# Bus.net
KiCad netlist of a schematic drawn in Altium Designer
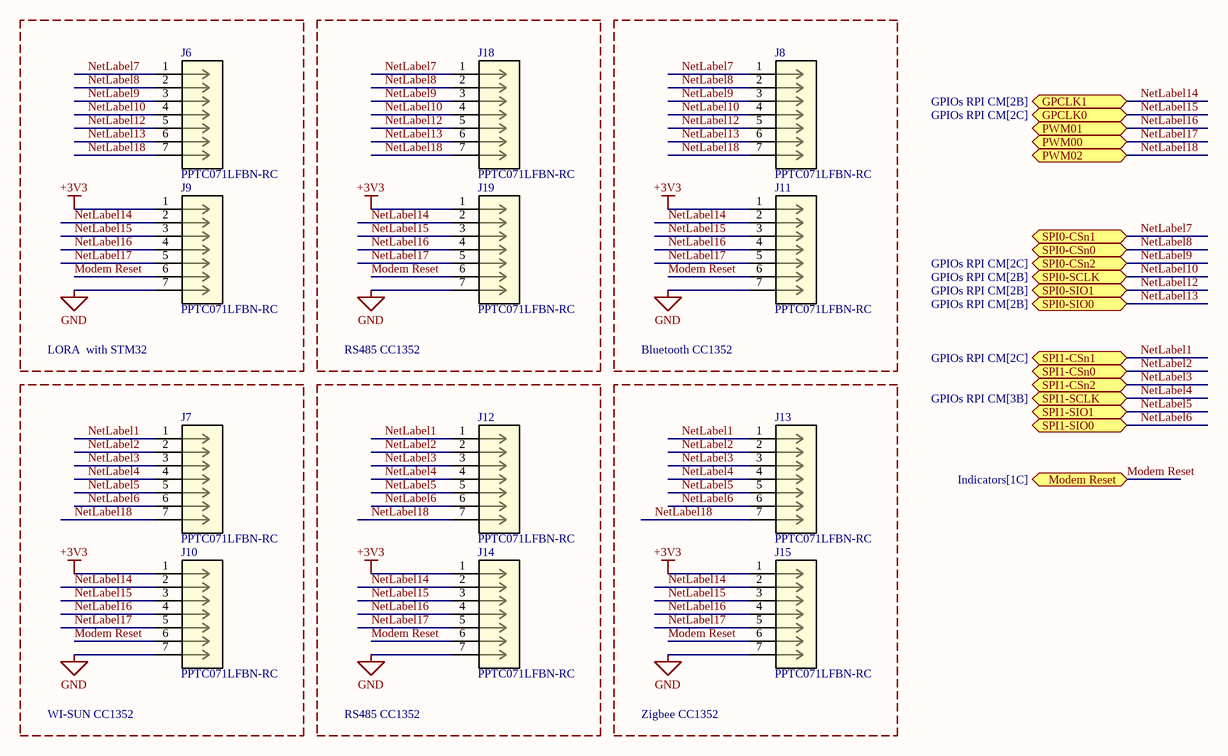
[diagram p0: Bus.SchDoc]

(export (version "E")
  (design (tool "Eeschema 10.0.6"))
  (components
    (comp (ref "J6")
      (value "PPTC071LFBN-RC")
      (footprint "CONN_xPxC071LFBN-RC_SUL")
      (description "No Description Available")
      (libsource (lib "PPTC071LFBN-RC") (part "PPTC071LFBN-RC"))
    )
    (comp (ref "J7")
      (value "PPTC071LFBN-RC")
      (footprint "CONN_xPxC071LFBN-RC_SUL")
      (description "No Description Available")
      (libsource (lib "PPTC071LFBN-RC") (part "PPTC071LFBN-RC"))
    )
    (comp (ref "J8")
      (value "PPTC071LFBN-RC")
      (footprint "CONN_xPxC071LFBN-RC_SUL")
      (description "No Description Available")
      (libsource (lib "PPTC071LFBN-RC") (part "PPTC071LFBN-RC"))
    )
    (comp (ref "J9")
      (value "PPTC071LFBN-RC")
      (footprint "CONN_xPxC071LFBN-RC_SUL")
      (description "No Description Available")
      (libsource (lib "PPTC071LFBN-RC") (part "PPTC071LFBN-RC"))
    )
    (comp (ref "J10")
      (value "PPTC071LFBN-RC")
      (footprint "CONN_xPxC071LFBN-RC_SUL")
      (description "No Description Available")
      (libsource (lib "PPTC071LFBN-RC") (part "PPTC071LFBN-RC"))
    )
    (comp (ref "J11")
      (value "PPTC071LFBN-RC")
      (footprint "CONN_xPxC071LFBN-RC_SUL")
      (description "No Description Available")
      (libsource (lib "PPTC071LFBN-RC") (part "PPTC071LFBN-RC"))
    )
    (comp (ref "J12")
      (value "PPTC071LFBN-RC")
      (footprint "CONN_xPxC071LFBN-RC_SUL")
      (description "No Description Available")
      (libsource (lib "PPTC071LFBN-RC") (part "PPTC071LFBN-RC"))
    )
    (comp (ref "J13")
      (value "PPTC071LFBN-RC")
      (footprint "CONN_xPxC071LFBN-RC_SUL")
      (description "No Description Available")
      (libsource (lib "PPTC071LFBN-RC") (part "PPTC071LFBN-RC"))
    )
    (comp (ref "J14")
      (value "PPTC071LFBN-RC")
      (footprint "CONN_xPxC071LFBN-RC_SUL")
      (description "No Description Available")
      (libsource (lib "PPTC071LFBN-RC") (part "PPTC071LFBN-RC"))
    )
    (comp (ref "J15")
      (value "PPTC071LFBN-RC")
      (footprint "CONN_xPxC071LFBN-RC_SUL")
      (description "No Description Available")
      (libsource (lib "PPTC071LFBN-RC") (part "PPTC071LFBN-RC"))
    )
    (comp (ref "J18")
      (value "PPTC071LFBN-RC")
      (footprint "CONN_xPxC071LFBN-RC_SUL")
      (description "No Description Available")
      (libsource (lib "PPTC071LFBN-RC") (part "PPTC071LFBN-RC"))
    )
    (comp (ref "J19")
      (value "PPTC071LFBN-RC")
      (footprint "CONN_xPxC071LFBN-RC_SUL")
      (description "No Description Available")
      (libsource (lib "PPTC071LFBN-RC") (part "PPTC071LFBN-RC"))
    )
  )
  (nets
    (net (code "1") (name "+3V3") (class "Default")
      (node (ref "J10") (pin "1") (pinfunction "1_1") (pintype "passive"))
      (node (ref "J11") (pin "1") (pinfunction "1_1") (pintype "passive"))
      (node (ref "J14") (pin "1") (pinfunction "1_1") (pintype "passive"))
      (node (ref "J15") (pin "1") (pinfunction "1_1") (pintype "passive"))
      (node (ref "J19") (pin "1") (pinfunction "1_1") (pintype "passive"))
      (node (ref "J9") (pin "1") (pinfunction "1_1") (pintype "passive"))
    )
    (net (code "2") (name "/Modem Reset") (class "Default")
      (node (ref "J10") (pin "6") (pinfunction "6_6") (pintype "passive"))
      (node (ref "J11") (pin "6") (pinfunction "6_6") (pintype "passive"))
      (node (ref "J14") (pin "6") (pinfunction "6_6") (pintype "passive"))
      (node (ref "J15") (pin "6") (pinfunction "6_6") (pintype "passive"))
      (node (ref "J19") (pin "6") (pinfunction "6_6") (pintype "passive"))
      (node (ref "J9") (pin "6") (pinfunction "6_6") (pintype "passive"))
    )
    (net (code "3") (name "/NetLabel1") (class "Default")
      (node (ref "J12") (pin "1") (pinfunction "1_1") (pintype "passive"))
      (node (ref "J13") (pin "1") (pinfunction "1_1") (pintype "passive"))
      (node (ref "J7") (pin "1") (pinfunction "1_1") (pintype "passive"))
    )
    (net (code "4") (name "/NetLabel2") (class "Default")
      (node (ref "J12") (pin "2") (pinfunction "2_2") (pintype "passive"))
      (node (ref "J13") (pin "2") (pinfunction "2_2") (pintype "passive"))
      (node (ref "J7") (pin "2") (pinfunction "2_2") (pintype "passive"))
    )
    (net (code "5") (name "/NetLabel3") (class "Default")
      (node (ref "J12") (pin "3") (pinfunction "3_3") (pintype "passive"))
      (node (ref "J13") (pin "3") (pinfunction "3_3") (pintype "passive"))
      (node (ref "J7") (pin "3") (pinfunction "3_3") (pintype "passive"))
    )
    (net (code "6") (name "/NetLabel4") (class "Default")
      (node (ref "J12") (pin "4") (pinfunction "4_4") (pintype "passive"))
      (node (ref "J13") (pin "4") (pinfunction "4_4") (pintype "passive"))
      (node (ref "J7") (pin "4") (pinfunction "4_4") (pintype "passive"))
    )
    (net (code "7") (name "/NetLabel5") (class "Default")
      (node (ref "J12") (pin "5") (pinfunction "5_5") (pintype "passive"))
      (node (ref "J13") (pin "5") (pinfunction "5_5") (pintype "passive"))
      (node (ref "J7") (pin "5") (pinfunction "5_5") (pintype "passive"))
    )
    (net (code "8") (name "/NetLabel6") (class "Default")
      (node (ref "J12") (pin "6") (pinfunction "6_6") (pintype "passive"))
      (node (ref "J13") (pin "6") (pinfunction "6_6") (pintype "passive"))
      (node (ref "J7") (pin "6") (pinfunction "6_6") (pintype "passive"))
    )
    (net (code "9") (name "/NetLabel7") (class "Default")
      (node (ref "J18") (pin "1") (pinfunction "1_1") (pintype "passive"))
      (node (ref "J6") (pin "1") (pinfunction "1_1") (pintype "passive"))
      (node (ref "J8") (pin "1") (pinfunction "1_1") (pintype "passive"))
    )
    (net (code "10") (name "/NetLabel8") (class "Default")
      (node (ref "J18") (pin "2") (pinfunction "2_2") (pintype "passive"))
      (node (ref "J6") (pin "2") (pinfunction "2_2") (pintype "passive"))
      (node (ref "J8") (pin "2") (pinfunction "2_2") (pintype "passive"))
    )
    (net (code "11") (name "/NetLabel9") (class "Default")
      (node (ref "J18") (pin "3") (pinfunction "3_3") (pintype "passive"))
      (node (ref "J6") (pin "3") (pinfunction "3_3") (pintype "passive"))
      (node (ref "J8") (pin "3") (pinfunction "3_3") (pintype "passive"))
    )
    (net (code "12") (name "/NetLabel10") (class "Default")
      (node (ref "J18") (pin "4") (pinfunction "4_4") (pintype "passive"))
      (node (ref "J6") (pin "4") (pinfunction "4_4") (pintype "passive"))
      (node (ref "J8") (pin "4") (pinfunction "4_4") (pintype "passive"))
    )
    (net (code "13") (name "/NetLabel12") (class "Default")
      (node (ref "J18") (pin "5") (pinfunction "5_5") (pintype "passive"))
      (node (ref "J6") (pin "5") (pinfunction "5_5") (pintype "passive"))
      (node (ref "J8") (pin "5") (pinfunction "5_5") (pintype "passive"))
    )
    (net (code "14") (name "/NetLabel13") (class "Default")
      (node (ref "J18") (pin "6") (pinfunction "6_6") (pintype "passive"))
      (node (ref "J6") (pin "6") (pinfunction "6_6") (pintype "passive"))
      (node (ref "J8") (pin "6") (pinfunction "6_6") (pintype "passive"))
    )
    (net (code "15") (name "/NetLabel14") (class "Default")
      (node (ref "J10") (pin "2") (pinfunction "2_2") (pintype "passive"))
      (node (ref "J11") (pin "2") (pinfunction "2_2") (pintype "passive"))
      (node (ref "J14") (pin "2") (pinfunction "2_2") (pintype "passive"))
      (node (ref "J15") (pin "2") (pinfunction "2_2") (pintype "passive"))
      (node (ref "J19") (pin "2") (pinfunction "2_2") (pintype "passive"))
      (node (ref "J9") (pin "2") (pinfunction "2_2") (pintype "passive"))
    )
    (net (code "16") (name "/NetLabel15") (class "Default")
      (node (ref "J10") (pin "3") (pinfunction "3_3") (pintype "passive"))
      (node (ref "J11") (pin "3") (pinfunction "3_3") (pintype "passive"))
      (node (ref "J14") (pin "3") (pinfunction "3_3") (pintype "passive"))
      (node (ref "J15") (pin "3") (pinfunction "3_3") (pintype "passive"))
      (node (ref "J19") (pin "3") (pinfunction "3_3") (pintype "passive"))
      (node (ref "J9") (pin "3") (pinfunction "3_3") (pintype "passive"))
    )
    (net (code "17") (name "/NetLabel16") (class "Default")
      (node (ref "J10") (pin "4") (pinfunction "4_4") (pintype "passive"))
      (node (ref "J11") (pin "4") (pinfunction "4_4") (pintype "passive"))
      (node (ref "J14") (pin "4") (pinfunction "4_4") (pintype "passive"))
      (node (ref "J15") (pin "4") (pinfunction "4_4") (pintype "passive"))
      (node (ref "J19") (pin "4") (pinfunction "4_4") (pintype "passive"))
      (node (ref "J9") (pin "4") (pinfunction "4_4") (pintype "passive"))
    )
    (net (code "18") (name "/NetLabel17") (class "Default")
      (node (ref "J10") (pin "5") (pinfunction "5_5") (pintype "passive"))
      (node (ref "J11") (pin "5") (pinfunction "5_5") (pintype "passive"))
      (node (ref "J14") (pin "5") (pinfunction "5_5") (pintype "passive"))
      (node (ref "J15") (pin "5") (pinfunction "5_5") (pintype "passive"))
      (node (ref "J19") (pin "5") (pinfunction "5_5") (pintype "passive"))
      (node (ref "J9") (pin "5") (pinfunction "5_5") (pintype "passive"))
    )
    (net (code "19") (name "/NetLabel18") (class "Default")
      (node (ref "J12") (pin "7") (pinfunction "7_7") (pintype "passive"))
      (node (ref "J13") (pin "7") (pinfunction "7_7") (pintype "passive"))
      (node (ref "J18") (pin "7") (pinfunction "7_7") (pintype "passive"))
      (node (ref "J6") (pin "7") (pinfunction "7_7") (pintype "passive"))
      (node (ref "J7") (pin "7") (pinfunction "7_7") (pintype "passive"))
      (node (ref "J8") (pin "7") (pinfunction "7_7") (pintype "passive"))
    )
    (net (code "20") (name "GND") (class "Default")
      (node (ref "J10") (pin "7") (pinfunction "7_7") (pintype "passive"))
      (node (ref "J11") (pin "7") (pinfunction "7_7") (pintype "passive"))
      (node (ref "J14") (pin "7") (pinfunction "7_7") (pintype "passive"))
      (node (ref "J15") (pin "7") (pinfunction "7_7") (pintype "passive"))
      (node (ref "J19") (pin "7") (pinfunction "7_7") (pintype "passive"))
      (node (ref "J9") (pin "7") (pinfunction "7_7") (pintype "passive"))
    )
  )
)
